# RS232_ISOLATED.net
KiCad netlist of a schematic drawn in Altium Designer
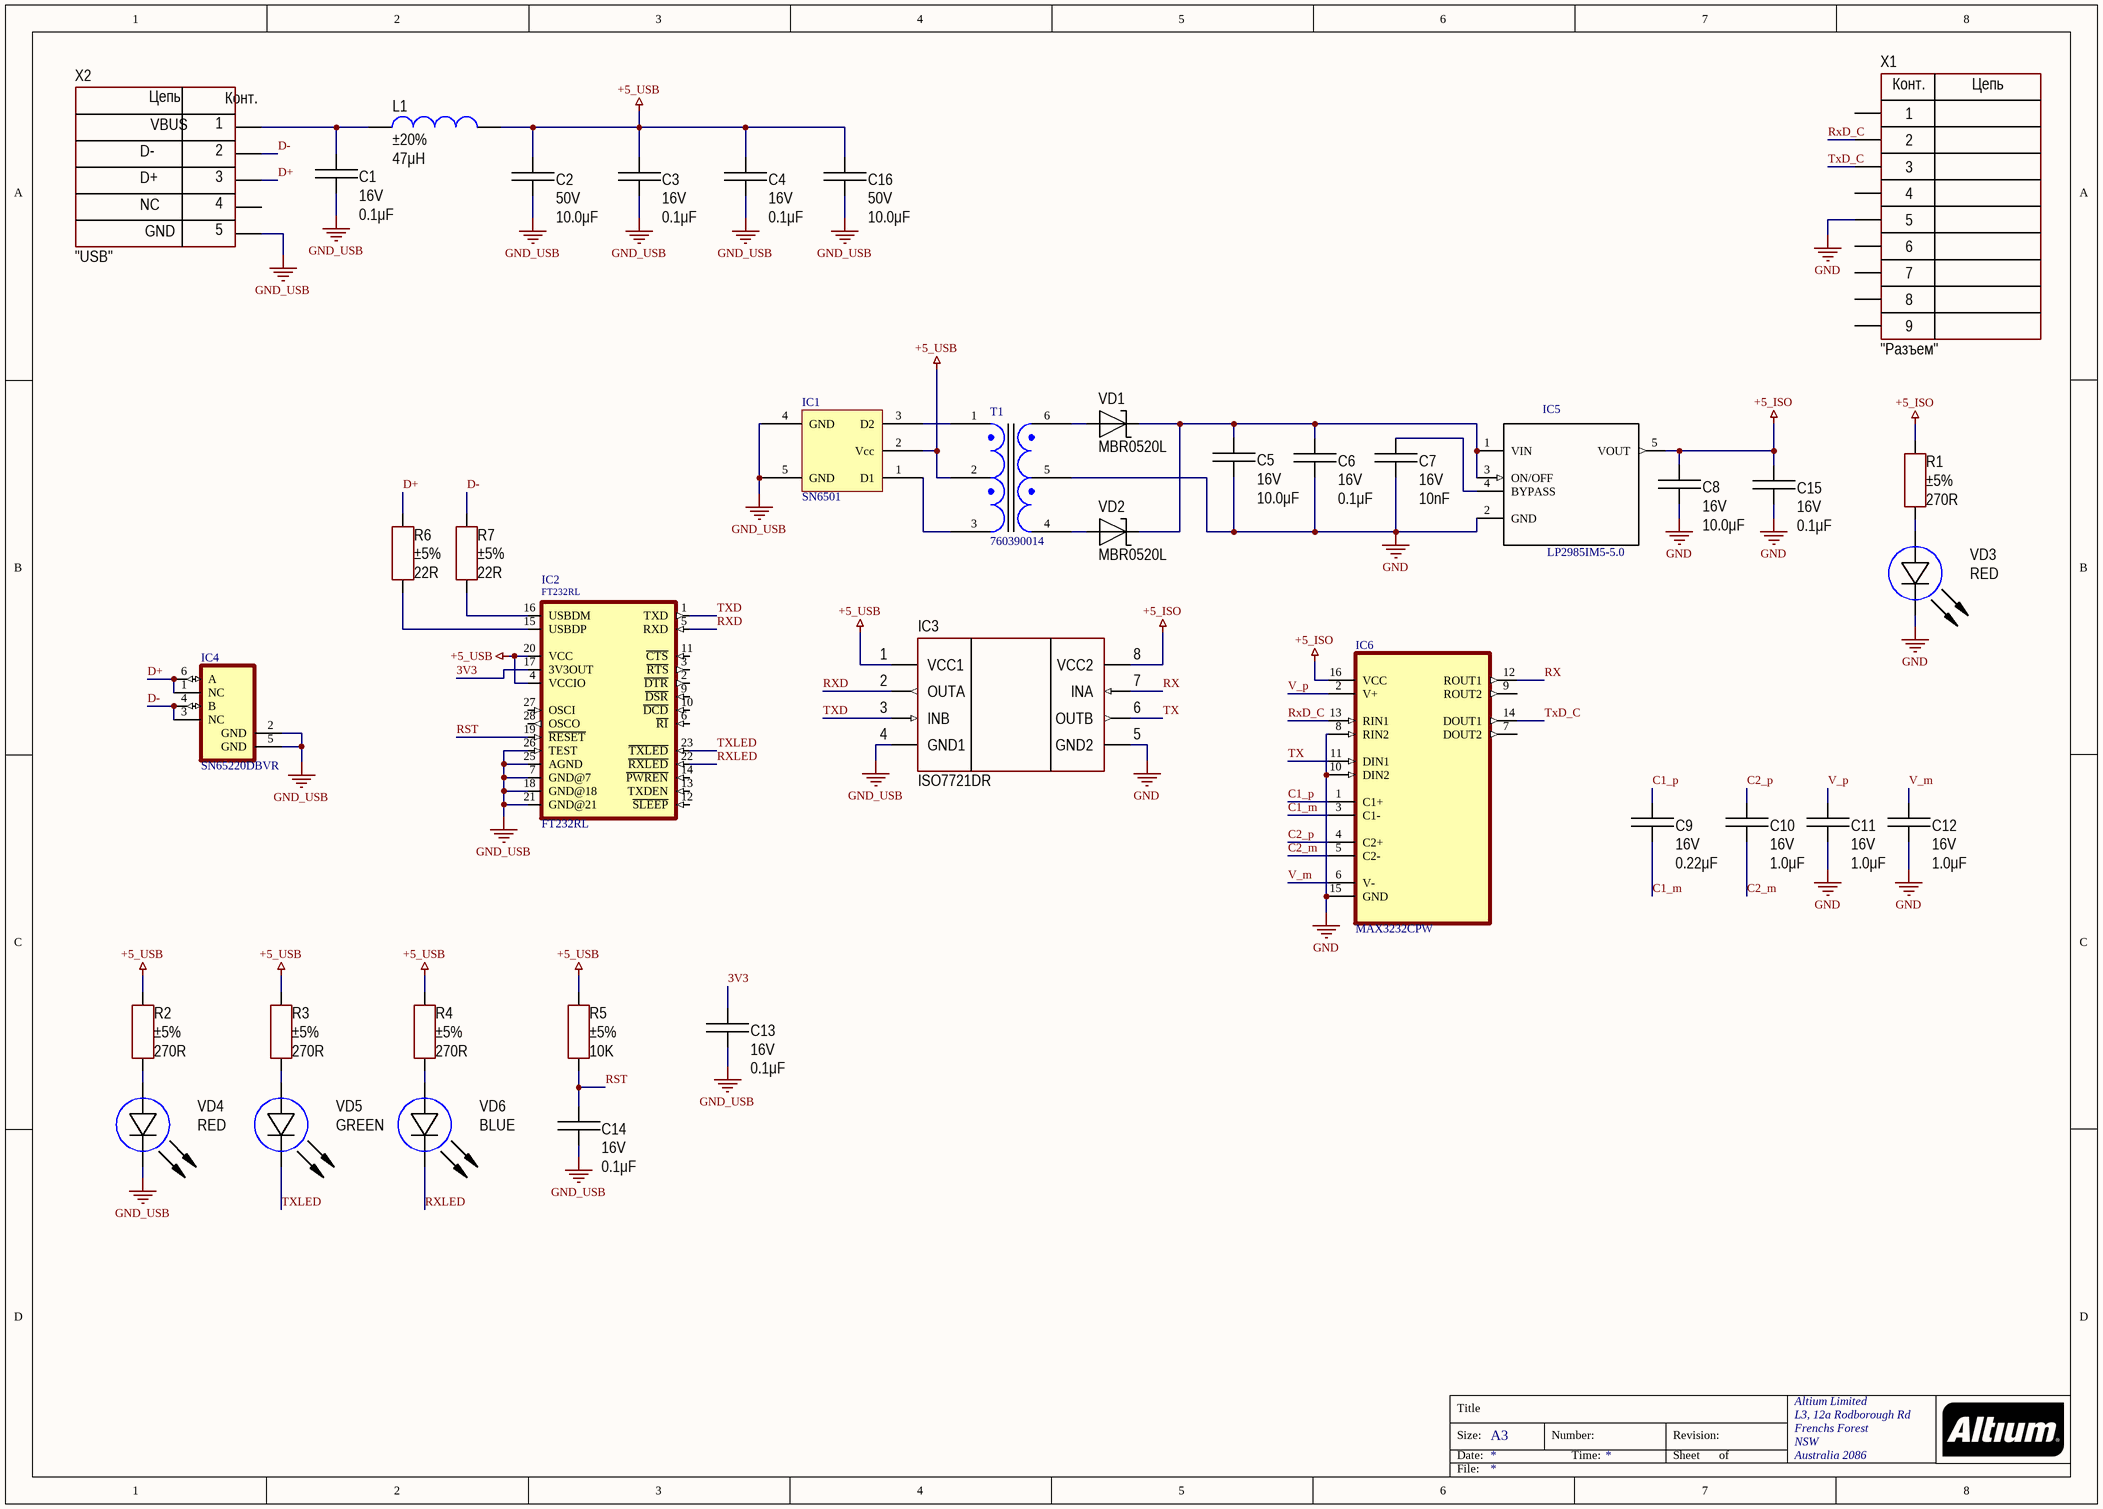
[diagram p0: RS232_ISOLATED.SchDoc]

(export (version "E")
  (design (tool "Eeschema 10.0.6"))
  (components
    (comp (ref "C1")
      (value "0.1μF")
      (footprint "StandardCase:CAP: 0805")
      (fields
        (field (name "MANUFACTURER") "Yageo")
        (field (name "PARTNUMBER") "CC0805KRX7R7BB104")
        (field (name "VALUEMANUFACTURERPARTNUMBER") "Ceramic capacitor, 0.1μF, X7R, ±10%, 16V, 0805, -55...+125°C")
        (field (name "VOLTAGE") "16V")
      )
      (libsource (lib "Capacitor") (part "Ceramic_0805"))
    )
    (comp (ref "C2")
      (value "10.0μF")
      (footprint "StandardCase:CAP: 1206")
      (fields
        (field (name "MANUFACTURER") "Yageo")
        (field (name "PARTNUMBER") "CC1206KRX7R9BB104")
        (field (name "VALUEMANUFACTURERPARTNUMBER") "Ceramic capacitor, 10.0μF, X7R, ±10%, 50V, 1206, -55...+125°C")
        (field (name "VOLTAGE") "50V")
      )
      (libsource (lib "Capacitor") (part "Ceramic_1206"))
    )
    (comp (ref "C3")
      (value "0.1μF")
      (footprint "StandardCase:CAP: 0805")
      (fields
        (field (name "MANUFACTURER") "Yageo")
        (field (name "PARTNUMBER") "CC0805KRX7R7BB104")
        (field (name "VALUEMANUFACTURERPARTNUMBER") "Ceramic capacitor, 0.1μF, X7R, ±10%, 16V, 0805, -55...+125°C")
        (field (name "VOLTAGE") "16V")
      )
      (libsource (lib "Capacitor") (part "Ceramic_0805"))
    )
    (comp (ref "C4")
      (value "0.1μF")
      (footprint "StandardCase:CAP: 0603")
      (fields
        (field (name "MANUFACTURER") "Yageo")
        (field (name "PARTNUMBER") "CC0805KRX7R7BB104")
        (field (name "VALUEMANUFACTURERPARTNUMBER") "Ceramic capacitor, 0.1μF, X7R, ±10%, 16V, 0805, -55...+125°C")
        (field (name "VOLTAGE") "16V")
      )
      (libsource (lib "Capacitor") (part "Ceramic_0805"))
    )
    (comp (ref "C5")
      (value "10.0μF")
      (footprint "StandardCase:CAP: 0805")
      (fields
        (field (name "MANUFACTURER") "Yageo")
        (field (name "PARTNUMBER") "CC0805KRX7R7BB104")
        (field (name "VALUEMANUFACTURERPARTNUMBER") "Ceramic capacitor, 10.0μF, X7R, ±10%, 16V, 0805, -55...+125°C")
        (field (name "VOLTAGE") "16V")
      )
      (libsource (lib "Capacitor") (part "Ceramic_0805"))
    )
    (comp (ref "C6")
      (value "0.1μF")
      (footprint "StandardCase:CAP: 0805")
      (fields
        (field (name "MANUFACTURER") "Yageo")
        (field (name "PARTNUMBER") "CC0805KRX7R7BB104")
        (field (name "VALUEMANUFACTURERPARTNUMBER") "Ceramic capacitor, 0.1μF, X7R, ±10%, 16V, 0805, -55...+125°C")
        (field (name "VOLTAGE") "16V")
      )
      (libsource (lib "Capacitor") (part "Ceramic_0805"))
    )
    (comp (ref "C7")
      (value "10nF")
      (footprint "StandardCase:CAP: 0603")
      (fields
        (field (name "MANUFACTURER") "Yageo")
        (field (name "PARTNUMBER") "CC0603KRX7R7BB104")
        (field (name "VALUEMANUFACTURERPARTNUMBER") "Ceramic capacitor, 10nF, X7R, ±10%, 16V, 0603, -55...+125°C")
        (field (name "VOLTAGE") "16V")
      )
      (libsource (lib "Capacitor") (part "Ceramic_0603"))
    )
    (comp (ref "C8")
      (value "10.0μF")
      (footprint "StandardCase:CAP: 0805")
      (fields
        (field (name "MANUFACTURER") "Yageo")
        (field (name "PARTNUMBER") "CC0805KRX7R7BB104")
        (field (name "VALUEMANUFACTURERPARTNUMBER") "Ceramic capacitor, 10.0μF, X7R, ±10%, 16V, 0805, -55...+125°C")
        (field (name "VOLTAGE") "16V")
      )
      (libsource (lib "Capacitor") (part "Ceramic_0805"))
    )
    (comp (ref "C9")
      (value "0.22μF")
      (footprint "StandardCase:CAP: 0603")
      (fields
        (field (name "MANUFACTURER") "Yageo")
        (field (name "PARTNUMBER") "CC0603KRX7R7BB104")
        (field (name "VALUEMANUFACTURERPARTNUMBER") "Ceramic capacitor, 0.22μF, X7R, ±10%, 16V, 0603, -55...+125°C")
        (field (name "VOLTAGE") "16V")
      )
      (libsource (lib "Capacitor") (part "Ceramic_0603"))
    )
    (comp (ref "C10")
      (value "1.0μF")
      (footprint "StandardCase:CAP: 0603")
      (fields
        (field (name "MANUFACTURER") "Yageo")
        (field (name "PARTNUMBER") "CC0603KRX7R7BB104")
        (field (name "VALUEMANUFACTURERPARTNUMBER") "Ceramic capacitor, 1.0μF, X7R, ±10%, 16V, 0603, -55...+125°C")
        (field (name "VOLTAGE") "16V")
      )
      (libsource (lib "Capacitor") (part "Ceramic_0603"))
    )
    (comp (ref "C11")
      (value "1.0μF")
      (footprint "StandardCase:CAP: 0603")
      (fields
        (field (name "MANUFACTURER") "Yageo")
        (field (name "PARTNUMBER") "CC0603KRX7R7BB104")
        (field (name "VALUEMANUFACTURERPARTNUMBER") "Ceramic capacitor, 1.0μF, X7R, ±10%, 16V, 0603, -55...+125°C")
        (field (name "VOLTAGE") "16V")
      )
      (libsource (lib "Capacitor") (part "Ceramic_0603"))
    )
    (comp (ref "C12")
      (value "1.0μF")
      (footprint "StandardCase:CAP: 0603")
      (fields
        (field (name "MANUFACTURER") "Yageo")
        (field (name "PARTNUMBER") "CC0603KRX7R7BB104")
        (field (name "VALUEMANUFACTURERPARTNUMBER") "Ceramic capacitor, 1.0μF, X7R, ±10%, 16V, 0603, -55...+125°C")
        (field (name "VOLTAGE") "16V")
      )
      (libsource (lib "Capacitor") (part "Ceramic_0603"))
    )
    (comp (ref "C13")
      (value "0.1μF")
      (footprint "StandardCase:CAP: 0603")
      (fields
        (field (name "MANUFACTURER") "Yageo")
        (field (name "PARTNUMBER") "CC0603KRX7R7BB104")
        (field (name "VALUEMANUFACTURERPARTNUMBER") "Ceramic capacitor, 0.1μF, X7R, ±10%, 16V, 0603, -55...+125°C")
        (field (name "VOLTAGE") "16V")
      )
      (libsource (lib "Capacitor") (part "Ceramic_0603"))
    )
    (comp (ref "C14")
      (value "0.1μF")
      (footprint "StandardCase:CAP: 0603")
      (fields
        (field (name "MANUFACTURER") "Yageo")
        (field (name "PARTNUMBER") "CC0603KRX7R7BB104")
        (field (name "VALUEMANUFACTURERPARTNUMBER") "Ceramic capacitor, 0.1μF, X7R, ±10%, 16V, 0603, -55...+125°C")
        (field (name "VOLTAGE") "16V")
      )
      (libsource (lib "Capacitor") (part "Ceramic_0603"))
    )
    (comp (ref "C15")
      (value "0.1μF")
      (footprint "StandardCase:CAP: 0805")
      (fields
        (field (name "MANUFACTURER") "Yageo")
        (field (name "PARTNUMBER") "CC0805KRX7R7BB104")
        (field (name "VALUEMANUFACTURERPARTNUMBER") "Ceramic capacitor, 0.1μF, X7R, ±10%, 16V, 0805, -55...+125°C")
        (field (name "VOLTAGE") "16V")
      )
      (libsource (lib "Capacitor") (part "Ceramic_0805"))
    )
    (comp (ref "C16")
      (value "10.0μF")
      (footprint "StandardCase:CAP: 1206")
      (fields
        (field (name "MANUFACTURER") "Yageo")
        (field (name "PARTNUMBER") "CC1206KRX7R9BB104")
        (field (name "VALUEMANUFACTURERPARTNUMBER") "Ceramic capacitor, 10.0μF, X7R, ±10%, 50V, 1206, -55...+125°C")
        (field (name "VOLTAGE") "50V")
      )
      (libsource (lib "Capacitor") (part "Ceramic_1206"))
    )
    (comp (ref "IC1")
      (value "SN6501")
      (footprint "StandardCase:SOT23-5")
      (libsource (lib "SN6501") (part "SN6501"))
    )
    (comp (ref "IC2")
      (value "FT232RL")
      (footprint "StandardCase:28-SSOP")
      (description "USB ë¸Œë¦¬ì§€, USB-UART USB 2.0 UART ì¸í„°íŽ˜ì´ìŠ¤ 28-SSOP")
      (fields (field (name "MF") "FTDI, Future"))
      (libsource (lib "FT232RL") (part "FT232RL"))
    )
    (comp (ref "IC3")
      (value "~")
      (footprint "StandardCase:8-SOIC")
      (description "Digital isolator")
      (fields
        (field (name "MANUFACTURER") "Texas Instruments")
        (field (name "VALUEMANUFACTURERPARTNUMBER") "IC digital isolator, 100Mbps, 3000Vrms, 2.25...5.5V, -55...+125°C, 8-SOIC")
        (field (name "PARTNUMBER") "ISO7721DR")
      )
      (libsource (lib "IC. Interface") (part "ISO7721DR"))
    )
    (comp (ref "IC4")
      (value "SN65220DBVR")
      (footprint "StandardCase:SOT23-6")
      (description "IC SINGLE USB PORT TVS SOT-23-6")
      (fields (field (name "MF") "Texas Instruments"))
      (libsource (lib "SN65220DBVR") (part "SN65220DBVR"))
    )
    (comp (ref "IC5")
      (value "LP2985IM5-5.0")
      (footprint "StandardCase:SOT23-5")
      (libsource (lib "LP2985IM5-5.0") (part "LP2985IM5-5.0"))
    )
    (comp (ref "IC6")
      (value "MAX3232CPW")
      (footprint "MAX3232CPW:SOP65P640X120-16N")
      (description "2/2 Transceiver Full RS232 16-TSSOP")
      (fields (field (name "MF") "Texas Instruments"))
      (libsource (lib "MAX3232CPW") (part "MAX3232CPW"))
    )
    (comp (ref "L1")
      (value "47μH")
      (footprint "StandardCase:IND: 0805")
      (fields
        (field (name "MANUFACTURER") "Murata Electronics")
        (field (name "PARTNUMBER") "LQM21FN100M70L")
        (field (name "VALUEMANUFACTURERPARTNUMBER") "Fixed inductor, 47μH, ±20%, 0805, 100mA, -55...+125°C")
        (field (name "TOLERANCE") "±20%")
      )
      (libsource (lib "Inductor") (part "Inductor_0805"))
    )
    (comp (ref "R1")
      (value "270R")
      (footprint "StandardCase:RES: 0603")
      (fields
        (field (name "MANUFACTURER") "Yageo")
        (field (name "PARTNUMBER") "RC0603JR-07100RL")
        (field (name "VALUEMANUFACTURERPARTNUMBER") "Resistor film, 270R, ±5%, 0603, 0.1W, -55...+125°C")
        (field (name "TOLERANCE") "±5%")
      )
      (libsource (lib "Resistor") (part "Resistor_0603"))
    )
    (comp (ref "R2")
      (value "270R")
      (footprint "StandardCase:RES: 0603")
      (fields
        (field (name "MANUFACTURER") "Yageo")
        (field (name "PARTNUMBER") "RC0603JR-07100RL")
        (field (name "VALUEMANUFACTURERPARTNUMBER") "Resistor film, 270R, ±5%, 0603, 0.1W, -55...+125°C")
        (field (name "TOLERANCE") "±5%")
      )
      (libsource (lib "Resistor") (part "Resistor_0603"))
    )
    (comp (ref "R3")
      (value "270R")
      (footprint "StandardCase:RES: 0603")
      (fields
        (field (name "MANUFACTURER") "Yageo")
        (field (name "PARTNUMBER") "RC0603JR-07100RL")
        (field (name "VALUEMANUFACTURERPARTNUMBER") "Resistor film, 270R, ±5%, 0603, 0.1W, -55...+125°C")
        (field (name "TOLERANCE") "±5%")
      )
      (libsource (lib "Resistor") (part "Resistor_0603"))
    )
    (comp (ref "R4")
      (value "270R")
      (footprint "StandardCase:RES: 0603")
      (fields
        (field (name "MANUFACTURER") "Yageo")
        (field (name "PARTNUMBER") "RC0603JR-07100RL")
        (field (name "VALUEMANUFACTURERPARTNUMBER") "Resistor film, 270R, ±5%, 0603, 0.1W, -55...+125°C")
        (field (name "TOLERANCE") "±5%")
      )
      (libsource (lib "Resistor") (part "Resistor_0603"))
    )
    (comp (ref "R5")
      (value "10K")
      (footprint "StandardCase:RES: 0603")
      (fields
        (field (name "MANUFACTURER") "Yageo")
        (field (name "PARTNUMBER") "RC0603JR-07100RL")
        (field (name "VALUEMANUFACTURERPARTNUMBER") "Resistor film, 10K, ±5%, 0603, 0.1W, -55...+125°C")
        (field (name "TOLERANCE") "±5%")
      )
      (libsource (lib "Resistor") (part "Resistor_0603"))
    )
    (comp (ref "R6")
      (value "22R")
      (footprint "StandardCase:RES: 0603")
      (fields
        (field (name "MANUFACTURER") "Yageo")
        (field (name "PARTNUMBER") "RC0603JR-07100RL")
        (field (name "VALUEMANUFACTURERPARTNUMBER") "Resistor film, 22R, ±5%, 0603, 0.1W, -55...+125°C")
        (field (name "TOLERANCE") "±5%")
      )
      (libsource (lib "Resistor") (part "Resistor_0603"))
    )
    (comp (ref "R7")
      (value "22R")
      (footprint "StandardCase:RES: 0603")
      (fields
        (field (name "MANUFACTURER") "Yageo")
        (field (name "PARTNUMBER") "RC0603JR-07100RL")
        (field (name "VALUEMANUFACTURERPARTNUMBER") "Resistor film, 22R, ±5%, 0603, 0.1W, -55...+125°C")
        (field (name "TOLERANCE") "±5%")
      )
      (libsource (lib "Resistor") (part "Resistor_0603"))
    )
    (comp (ref "T1")
      (value "760390014")
      (footprint "760390014:PCBComponent_1")
      (libsource (lib "760690014") (part "760390014"))
    )
    (comp (ref "VD1")
      (value "~")
      (footprint "StandardCase:DIODE: SOD123")
      (fields
        (field (name "MANUFACTURER") "Diodes Incorporated")
        (field (name "VALUEMANUFACTURERPARTNUMBER") "Schottky diode, 80V, 500mA, 1V, 15pF, SOD-123, -55...+150°C")
        (field (name "VOLTAGE") "80V")
        (field (name "PARTNUMBER") "MBR0520L")
      )
      (libsource (lib "Diode") (part "Schottky_single"))
    )
    (comp (ref "VD2")
      (value "~")
      (footprint "StandardCase:DIODE: SOD123")
      (fields
        (field (name "MANUFACTURER") "Diodes Incorporated")
        (field (name "VALUEMANUFACTURERPARTNUMBER") "Schottky diode, 80V, 500mA, 1V, 15pF, SOD-123, -55...+150°C")
        (field (name "VOLTAGE") "80V")
        (field (name "PARTNUMBER") "MBR0520L")
      )
      (libsource (lib "Diode") (part "Schottky_single"))
    )
    (comp (ref "VD3")
      (value "~")
      (footprint "StandardCase:LED: 0402B")
      (fields
        (field (name "VALUEMANUFACTURERPARTNUMBER") "LED, *, *, *, -55...+150°C")
        (field (name "COLOR") "RED")
      )
      (libsource (lib "Diode") (part "LED_single"))
    )
    (comp (ref "VD4")
      (value "~")
      (footprint "StandardCase:LED: 0402B")
      (fields
        (field (name "VALUEMANUFACTURERPARTNUMBER") "LED, *, *, *, -55...+150°C")
        (field (name "COLOR") "RED")
      )
      (libsource (lib "Diode") (part "LED_single"))
    )
    (comp (ref "VD5")
      (value "~")
      (footprint "StandardCase:LED: 0402B")
      (fields
        (field (name "VALUEMANUFACTURERPARTNUMBER") "LED, *, *, *, -55...+150°C")
        (field (name "COLOR") "GREEN")
      )
      (libsource (lib "Diode") (part "LED_single"))
    )
    (comp (ref "VD6")
      (value "~")
      (footprint "StandardCase:LED: 0402B")
      (fields
        (field (name "VALUEMANUFACTURERPARTNUMBER") "LED, *, *, *, -55...+150°C")
        (field (name "COLOR") "BLUE")
      )
      (libsource (lib "Diode") (part "LED_single"))
    )
    (comp (ref "X1")
      (value "~")
      (footprint "CustomCase:CON: DB-9M")
      (fields
        (field (name "MANUFACTURER") "Connfly")
        (field (name "VALUEMANUFACTURERPARTNUMBER") "Connector, 10pin, 2.54mm, 500VAC, 3A")
        (field (name "PARTNUMBER") "PBD-10")
        (field (name "COMMENTTEXT") "\"Разъем\"")
      )
      (libsource (lib "Connector") (part "Connector_DB9F"))
    )
    (comp (ref "X2")
      (value "~")
      (footprint "CustomCase:CON: 0675031020")
      (fields
        (field (name "MANUFACTURER") "Molex")
        (field (name "VALUEMANUFACTURERPARTNUMBER") "USB mini B")
        (field (name "PARTNUMBER") "0675031020")
        (field (name "COMMENTTEXT") "\"USB\"")
      )
      (libsource (lib "Connector") (part "Connector_USB_mini_B"))
    )
  )
  (nets
    (net (code "1") (name "+5_ISO") (class "Default")
      (node (ref "C15") (pin "2") (pinfunction "2_2") (pintype "power_in"))
      (node (ref "C8") (pin "2") (pinfunction "2_2") (pintype "power_in"))
      (node (ref "IC3") (pin "8") (pinfunction "VCC2_8") (pintype "passive"))
      (node (ref "IC5") (pin "5") (pinfunction "VOUT_5") (pintype "output"))
      (node (ref "IC6") (pin "16") (pinfunction "VCC_16") (pintype "power_in"))
      (node (ref "R1") (pin "2") (pinfunction "2_2") (pintype "passive"))
    )
    (net (code "2") (name "+5_USB") (class "Default")
      (node (ref "C16") (pin "2") (pinfunction "2_2") (pintype "power_in"))
      (node (ref "C2") (pin "2") (pinfunction "2_2") (pintype "power_in"))
      (node (ref "C3") (pin "2") (pinfunction "2_2") (pintype "power_in"))
      (node (ref "C4") (pin "2") (pinfunction "2_2") (pintype "power_in"))
      (node (ref "IC1") (pin "2") (pinfunction "Vcc_2") (pintype "passive"))
      (node (ref "IC2") (pin "20") (pinfunction "VCC_20") (pintype "power_in"))
      (node (ref "IC2") (pin "4") (pinfunction "VCCIO_4") (pintype "power_in"))
      (node (ref "IC3") (pin "1") (pinfunction "VCC1_1") (pintype "passive"))
      (node (ref "L1") (pin "1") (pinfunction "1_1") (pintype "passive"))
      (node (ref "R2") (pin "2") (pinfunction "2_2") (pintype "passive"))
      (node (ref "R3") (pin "2") (pinfunction "2_2") (pintype "passive"))
      (node (ref "R4") (pin "2") (pinfunction "2_2") (pintype "passive"))
      (node (ref "R5") (pin "2") (pinfunction "2_2") (pintype "passive"))
      (node (ref "T1") (pin "2") (pintype "passive"))
    )
    (net (code "3") (name "/3V3") (class "Default")
      (node (ref "C13") (pin "2") (pinfunction "2_2") (pintype "power_in"))
      (node (ref "IC2") (pin "17") (pinfunction "3V3OUT_17") (pintype "power_in"))
    )
    (net (code "4") (name "/C1_m") (class "Default")
      (node (ref "C9") (pin "1") (pinfunction "1_1") (pintype "power_in"))
      (node (ref "IC6") (pin "3") (pinfunction "C1-_3") (pintype "passive"))
    )
    (net (code "5") (name "/C1_p") (class "Default")
      (node (ref "C9") (pin "2") (pinfunction "2_2") (pintype "power_in"))
      (node (ref "IC6") (pin "1") (pinfunction "C1+_1") (pintype "passive"))
    )
    (net (code "6") (name "/C2_m") (class "Default")
      (node (ref "C10") (pin "1") (pinfunction "1_1") (pintype "power_in"))
      (node (ref "IC6") (pin "5") (pinfunction "C2-_5") (pintype "passive"))
    )
    (net (code "7") (name "/C2_p") (class "Default")
      (node (ref "C10") (pin "2") (pinfunction "2_2") (pintype "power_in"))
      (node (ref "IC6") (pin "4") (pinfunction "C2+_4") (pintype "passive"))
    )
    (net (code "8") (name "/D+") (class "Default")
      (node (ref "IC4") (pin "1") (pinfunction "NC_1") (pintype "passive"))
      (node (ref "IC4") (pin "6") (pinfunction "A_6") (pintype "bidirectional"))
      (node (ref "R6") (pin "2") (pinfunction "2_2") (pintype "passive"))
      (node (ref "X2") (pin "3") (pinfunction "3_3") (pintype "passive"))
    )
    (net (code "9") (name "/D-") (class "Default")
      (node (ref "IC4") (pin "3") (pinfunction "NC_3") (pintype "passive"))
      (node (ref "IC4") (pin "4") (pinfunction "B_4") (pintype "bidirectional"))
      (node (ref "R7") (pin "2") (pinfunction "2_2") (pintype "passive"))
      (node (ref "X2") (pin "2") (pinfunction "2_2") (pintype "passive"))
    )
    (net (code "10") (name "/RST") (class "Default")
      (node (ref "C14") (pin "2") (pinfunction "2_2") (pintype "power_in"))
      (node (ref "IC2") (pin "19") (pinfunction "~{RESET}_19") (pintype "input"))
      (node (ref "R5") (pin "1") (pinfunction "1_1") (pintype "passive"))
    )
    (net (code "11") (name "/RX") (class "Default")
      (node (ref "IC3") (pin "7") (pinfunction "INA_7") (pintype "input"))
      (node (ref "IC6") (pin "12") (pinfunction "ROUT1_12") (pintype "output"))
    )
    (net (code "12") (name "/RXD") (class "Default")
      (node (ref "IC2") (pin "5") (pinfunction "RXD_5") (pintype "input"))
      (node (ref "IC3") (pin "2") (pinfunction "OUTA_2") (pintype "output"))
    )
    (net (code "13") (name "/RXLED") (class "Default")
      (node (ref "IC2") (pin "22") (pinfunction "~{RXLED}_22") (pintype "input"))
      (node (ref "VD6") (pin "2") (pinfunction "C_2") (pintype "passive"))
    )
    (net (code "14") (name "/RxD_C") (class "Default")
      (node (ref "IC6") (pin "13") (pinfunction "RIN1_13") (pintype "input"))
      (node (ref "X1") (pin "2") (pinfunction "2_2") (pintype "passive"))
    )
    (net (code "15") (name "/TX") (class "Default")
      (node (ref "IC3") (pin "6") (pinfunction "OUTB_6") (pintype "output"))
      (node (ref "IC6") (pin "11") (pinfunction "DIN1_11") (pintype "input"))
    )
    (net (code "16") (name "/TXD") (class "Default")
      (node (ref "IC2") (pin "1") (pinfunction "TXD_1") (pintype "output"))
      (node (ref "IC3") (pin "3") (pinfunction "INB_3") (pintype "input"))
    )
    (net (code "17") (name "/TXLED") (class "Default")
      (node (ref "IC2") (pin "23") (pinfunction "~{TXLED}_23") (pintype "input"))
      (node (ref "VD5") (pin "2") (pinfunction "C_2") (pintype "passive"))
    )
    (net (code "18") (name "/TxD_C") (class "Default")
      (node (ref "IC6") (pin "14") (pinfunction "DOUT1_14") (pintype "output"))
      (node (ref "X1") (pin "3") (pinfunction "3_3") (pintype "power_in"))
    )
    (net (code "19") (name "/V_m") (class "Default")
      (node (ref "C12") (pin "2") (pinfunction "2_2") (pintype "power_in"))
      (node (ref "IC6") (pin "6") (pinfunction "V-_6") (pintype "power_in"))
    )
    (net (code "20") (name "/V_p") (class "Default")
      (node (ref "C11") (pin "2") (pinfunction "2_2") (pintype "power_in"))
      (node (ref "IC6") (pin "2") (pinfunction "V+_2") (pintype "power_in"))
    )
    (net (code "21") (name "GND") (class "Default")
      (node (ref "C11") (pin "1") (pinfunction "1_1") (pintype "power_in"))
      (node (ref "C12") (pin "1") (pinfunction "1_1") (pintype "power_in"))
      (node (ref "C15") (pin "1") (pinfunction "1_1") (pintype "power_in"))
      (node (ref "C5") (pin "1") (pinfunction "1_1") (pintype "power_in"))
      (node (ref "C6") (pin "1") (pinfunction "1_1") (pintype "power_in"))
      (node (ref "C7") (pin "1") (pinfunction "1_1") (pintype "power_in"))
      (node (ref "C8") (pin "1") (pinfunction "1_1") (pintype "power_in"))
      (node (ref "IC3") (pin "5") (pinfunction "GND2_5") (pintype "passive"))
      (node (ref "IC5") (pin "2") (pinfunction "GND_2") (pintype "passive"))
      (node (ref "IC6") (pin "10") (pinfunction "DIN2_10") (pintype "input"))
      (node (ref "IC6") (pin "15") (pinfunction "GND_15") (pintype "passive"))
      (node (ref "IC6") (pin "8") (pinfunction "RIN2_8") (pintype "input"))
      (node (ref "T1") (pin "5") (pintype "passive"))
      (node (ref "VD3") (pin "2") (pinfunction "C_2") (pintype "passive"))
      (node (ref "X1") (pin "5") (pinfunction "5_5") (pintype "power_in"))
    )
    (net (code "22") (name "GND_USB") (class "Default")
      (node (ref "C1") (pin "1") (pinfunction "1_1") (pintype "power_in"))
      (node (ref "C13") (pin "1") (pinfunction "1_1") (pintype "power_in"))
      (node (ref "C14") (pin "1") (pinfunction "1_1") (pintype "power_in"))
      (node (ref "C16") (pin "1") (pinfunction "1_1") (pintype "power_in"))
      (node (ref "C2") (pin "1") (pinfunction "1_1") (pintype "power_in"))
      (node (ref "C3") (pin "1") (pinfunction "1_1") (pintype "power_in"))
      (node (ref "C4") (pin "1") (pinfunction "1_1") (pintype "power_in"))
      (node (ref "IC1") (pin "4") (pinfunction "GND_4") (pintype "passive"))
      (node (ref "IC1") (pin "5") (pinfunction "GND_5") (pintype "passive"))
      (node (ref "IC2") (pin "18") (pinfunction "GND@18_18") (pintype "power_in"))
      (node (ref "IC2") (pin "21") (pinfunction "GND@21_21") (pintype "power_in"))
      (node (ref "IC2") (pin "25") (pinfunction "AGND_25") (pintype "power_in"))
      (node (ref "IC2") (pin "26") (pinfunction "TEST_26") (pintype "input"))
      (node (ref "IC2") (pin "7") (pinfunction "GND@7_7") (pintype "power_in"))
      (node (ref "IC3") (pin "4") (pinfunction "GND1_4") (pintype "passive"))
      (node (ref "IC4") (pin "2") (pinfunction "GND_2") (pintype "power_in"))
      (node (ref "IC4") (pin "5") (pinfunction "GND_5") (pintype "power_in"))
      (node (ref "VD4") (pin "2") (pinfunction "C_2") (pintype "passive"))
      (node (ref "X2") (pin "5") (pinfunction "5_5") (pintype "passive"))
    )
    (net (code "23") (name "Net-(C1-Pad2)") (class "Default")
      (node (ref "C1") (pin "2") (pinfunction "2_2") (pintype "power_in"))
      (node (ref "L1") (pin "2") (pinfunction "2_2") (pintype "passive"))
      (node (ref "X2") (pin "1") (pintype "passive"))
    )
    (net (code "24") (name "Net-(IC1-D1)") (class "Default")
      (node (ref "IC1") (pin "1") (pinfunction "D1_1") (pintype "passive"))
      (node (ref "T1") (pin "3") (pintype "passive"))
    )
    (net (code "25") (name "Net-(IC1-D2)") (class "Default")
      (node (ref "IC1") (pin "3") (pinfunction "D2_3") (pintype "passive"))
      (node (ref "T1") (pin "1") (pintype "passive"))
    )
    (net (code "26") (name "Net-(IC2-USBDM)") (class "Default")
      (node (ref "IC2") (pin "16") (pinfunction "USBDM_16") (pintype "bidirectional"))
      (node (ref "R7") (pin "1") (pinfunction "1_1") (pintype "passive"))
    )
    (net (code "27") (name "Net-(IC2-USBDP)") (class "Default")
      (node (ref "IC2") (pin "15") (pinfunction "USBDP_15") (pintype "bidirectional"))
      (node (ref "R6") (pin "1") (pinfunction "1_1") (pintype "passive"))
    )
    (net (code "28") (name "Net-(IC5-BYPASS)") (class "Default")
      (node (ref "C7") (pin "2") (pinfunction "2_2") (pintype "power_in"))
      (node (ref "IC5") (pin "4") (pinfunction "BYPASS_4") (pintype "passive"))
    )
    (net (code "29") (name "Net-(IC5-ON{slash}OFF)") (class "Default")
      (node (ref "C5") (pin "2") (pinfunction "2_2") (pintype "power_in"))
      (node (ref "C6") (pin "2") (pinfunction "2_2") (pintype "power_in"))
      (node (ref "IC5") (pin "1") (pinfunction "VIN_1") (pintype "power_in"))
      (node (ref "IC5") (pin "3") (pinfunction "ON/OFF_3") (pintype "input"))
      (node (ref "VD1") (pin "2") (pinfunction "2_2") (pintype "passive"))
      (node (ref "VD2") (pin "2") (pinfunction "2_2") (pintype "passive"))
    )
    (net (code "30") (name "Net-(T1-Pad4)") (class "Default")
      (node (ref "T1") (pin "4") (pintype "passive"))
      (node (ref "VD2") (pin "1") (pinfunction "1_1") (pintype "passive"))
    )
    (net (code "31") (name "Net-(T1-Pad6)") (class "Default")
      (node (ref "T1") (pin "6") (pintype "passive"))
      (node (ref "VD1") (pin "1") (pinfunction "1_1") (pintype "passive"))
    )
    (net (code "32") (name "Net-(VD3-A)") (class "Default")
      (node (ref "R1") (pin "1") (pinfunction "1_1") (pintype "passive"))
      (node (ref "VD3") (pin "1") (pinfunction "A_1") (pintype "passive"))
    )
    (net (code "33") (name "Net-(VD4-A)") (class "Default")
      (node (ref "R2") (pin "1") (pinfunction "1_1") (pintype "passive"))
      (node (ref "VD4") (pin "1") (pinfunction "A_1") (pintype "passive"))
    )
    (net (code "34") (name "Net-(VD5-A)") (class "Default")
      (node (ref "R3") (pin "1") (pinfunction "1_1") (pintype "passive"))
      (node (ref "VD5") (pin "1") (pinfunction "A_1") (pintype "passive"))
    )
    (net (code "35") (name "Net-(VD6-A)") (class "Default")
      (node (ref "R4") (pin "1") (pinfunction "1_1") (pintype "passive"))
      (node (ref "VD6") (pin "1") (pinfunction "A_1") (pintype "passive"))
    )
    (net (code "36") (name "unconnected-(IC2-OSCI-Pad27)") (class "Default")
      (node (ref "IC2") (pin "27") (pinfunction "OSCI_27") (pintype "input"))
    )
    (net (code "37") (name "unconnected-(IC2-OSCO-Pad28)") (class "Default")
      (node (ref "IC2") (pin "28") (pinfunction "OSCO_28") (pintype "output"))
    )
    (net (code "38") (name "unconnected-(IC2-TXDEN-Pad13)") (class "Default")
      (node (ref "IC2") (pin "13") (pinfunction "TXDEN_13") (pintype "input"))
    )
    (net (code "39") (name "unconnected-(IC2-~{CTS}-Pad11)") (class "Default")
      (node (ref "IC2") (pin "11") (pinfunction "~{CTS}_11") (pintype "input"))
    )
    (net (code "40") (name "unconnected-(IC2-~{DCD}-Pad10)") (class "Default")
      (node (ref "IC2") (pin "10") (pinfunction "~{DCD}_10") (pintype "input"))
    )
    (net (code "41") (name "unconnected-(IC2-~{DSR}-Pad9)") (class "Default")
      (node (ref "IC2") (pin "9") (pinfunction "~{DSR}_9") (pintype "input"))
    )
    (net (code "42") (name "unconnected-(IC2-~{DTR}-Pad2)") (class "Default")
      (node (ref "IC2") (pin "2") (pinfunction "~{DTR}_2") (pintype "output"))
    )
    (net (code "43") (name "unconnected-(IC2-~{PWREN}-Pad14)") (class "Default")
      (node (ref "IC2") (pin "14") (pinfunction "~{PWREN}_14") (pintype "input"))
    )
    (net (code "44") (name "unconnected-(IC2-~{RI}-Pad6)") (class "Default")
      (node (ref "IC2") (pin "6") (pinfunction "~{RI}_6") (pintype "input"))
    )
    (net (code "45") (name "unconnected-(IC2-~{RTS}-Pad3)") (class "Default")
      (node (ref "IC2") (pin "3") (pinfunction "~{RTS}_3") (pintype "output"))
    )
    (net (code "46") (name "unconnected-(IC2-~{SLEEP}-Pad12)") (class "Default")
      (node (ref "IC2") (pin "12") (pinfunction "~{SLEEP}_12") (pintype "input"))
    )
    (net (code "47") (name "unconnected-(IC6-DOUT2-Pad7)") (class "Default")
      (node (ref "IC6") (pin "7") (pinfunction "DOUT2_7") (pintype "output"))
    )
    (net (code "48") (name "unconnected-(IC6-ROUT2-Pad9)") (class "Default")
      (node (ref "IC6") (pin "9") (pinfunction "ROUT2_9") (pintype "output"))
    )
    (net (code "49") (name "unconnected-(X1-Pad1)") (class "Default")
      (node (ref "X1") (pin "1") (pinfunction "1_1") (pintype "passive"))
    )
    (net (code "50") (name "unconnected-(X1-Pad4)") (class "Default")
      (node (ref "X1") (pin "4") (pinfunction "4_4") (pintype "power_in"))
    )
    (net (code "51") (name "unconnected-(X1-Pad6)") (class "Default")
      (node (ref "X1") (pin "6") (pinfunction "6_6") (pintype "power_in"))
    )
    (net (code "52") (name "unconnected-(X1-Pad7)") (class "Default")
      (node (ref "X1") (pin "7") (pinfunction "7_7") (pintype "power_in"))
    )
    (net (code "53") (name "unconnected-(X1-Pad8)") (class "Default")
      (node (ref "X1") (pin "8") (pinfunction "8_8") (pintype "power_in"))
    )
    (net (code "54") (name "unconnected-(X1-Pad9)") (class "Default")
      (node (ref "X1") (pin "9") (pinfunction "9_9") (pintype "power_in"))
    )
    (net (code "55") (name "unconnected-(X2-Pad4)") (class "Default")
      (node (ref "X2") (pin "4") (pinfunction "4_4") (pintype "passive"))
    )
  )
)
